# 19_KEY_LED.net
KiCad netlist of a schematic drawn in Altium Designer
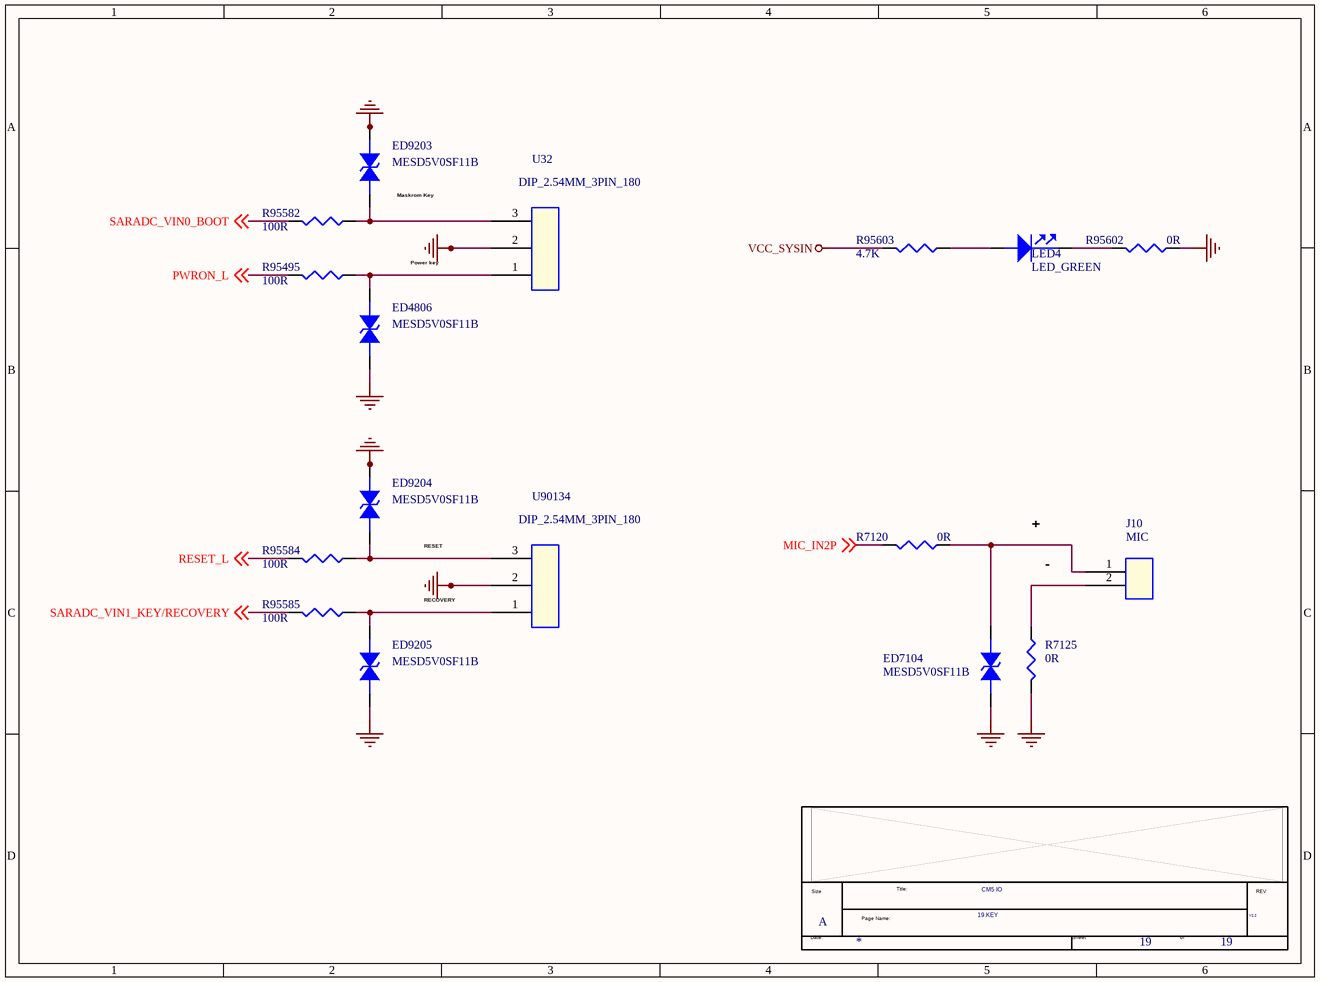
[diagram p0: 19_KEY_LED.SchDoc]

(export (version "E")
  (design (tool "Eeschema 10.0.6"))
  (components
    (comp (ref "*")
      (value "radxa_1010")
      (fields
        (field (name "DOC") "19.KEY")
        (field (name "REVCODE") "V2.2")
        (field (name "TITLE") "CM5 IO")
        (field (name "PAGE SIZE") "A")
        (field (name "PAGE NUMBER") "19")
        (field (name "PAGE COUNT") "19")
      )
      (libsource (lib "*") (part "radxa_1010"))
    )
    (comp (ref "ED4806")
      (value "MESD5V0SF11B")
      (footprint "E0402N")
      (description "ESD Component,5V,30P,SMD,0402")
      (libsource (lib "*") (part "TVS"))
    )
    (comp (ref "ED7104")
      (value "MESD5V0SF11B")
      (footprint "ESD0402")
      (description "1-Line, Bi-directional, Transient Voltage Suppressors.17.5pF.")
      (fields (field (name "MANUFACTURER") "WillSemi(韦尔半导体)") (field (name "CREATED BY") "JJJ"))
      (libsource (lib "*") (part "DIODE BI_DIR TRIG_2"))
    )
    (comp (ref "ED9203")
      (value "MESD5V0SF11B")
      (footprint "E0402N")
      (description "ESD Component,5V,30P,SMD,0402")
      (libsource (lib "*") (part "TVS"))
    )
    (comp (ref "ED9204")
      (value "MESD5V0SF11B")
      (footprint "E0402N")
      (description "ESD Component,5V,30P,SMD,0402")
      (libsource (lib "*") (part "TVS"))
    )
    (comp (ref "ED9205")
      (value "MESD5V0SF11B")
      (footprint "E0402N")
      (description "ESD Component,5V,30P,SMD,0402")
      (libsource (lib "*") (part "TVS"))
    )
    (comp (ref "J10") (value "MIC") (footprint "DIP2PIN-2P54MM") (libsource (lib "*") (part "CON2")))
    (comp (ref "LED4")
      (value "LED_GREEN")
      (footprint "LED0603")
      (description "贴片LED灯，0603，绿色")
      (fields (field (name "CREATED BY") "JJJ"))
      (libsource (lib "*") (part "LED"))
    )
    (comp (ref "R7120")
      (value "0R")
      (footprint "R0402")
      (description "通用厚膜电阻,0R,+/-5%,R0402,1/16W.")
      (fields
        (field (name "TOLERANCE") "5%")
        (field (name "MANUFACTURER") "YAGEO")
        (field (name "CREATED BY") "YTL")
      )
      (libsource (lib "*") (part "RESISTOR_1"))
    )
    (comp (ref "R7125")
      (value "0R")
      (footprint "R0402")
      (description "通用厚膜电阻,2K2,+/-1%,R0402,1/16W.")
      (fields
        (field (name "TOLERANCE") "1%")
        (field (name "MANUFACTURER") "YAGEO")
        (field (name "CREATED BY") "YTL")
      )
      (libsource (lib "*") (part "RESISTOR_1"))
    )
    (comp (ref "R95495")
      (value "100R")
      (footprint "R0402")
      (description "通用厚膜电阻,49K9,+/-1%,R0402,1/16W.")
      (fields
        (field (name "TOLERANCE") "1%")
        (field (name "MANUFACTURER") "YAGEO")
        (field (name "CREATED BY") "YTL")
      )
      (libsource (lib "*") (part "RESISTOR_1_Dup1"))
    )
    (comp (ref "R95582")
      (value "100R")
      (footprint "R0402")
      (description "通用厚膜电阻,49K9,+/-1%,R0402,1/16W.")
      (fields
        (field (name "TOLERANCE") "1%")
        (field (name "MANUFACTURER") "YAGEO")
        (field (name "CREATED BY") "YTL")
      )
      (libsource (lib "*") (part "RESISTOR_1_Dup1"))
    )
    (comp (ref "R95584")
      (value "100R")
      (footprint "R0402")
      (description "通用厚膜电阻,49K9,+/-1%,R0402,1/16W.")
      (fields
        (field (name "TOLERANCE") "1%")
        (field (name "MANUFACTURER") "YAGEO")
        (field (name "CREATED BY") "YTL")
      )
      (libsource (lib "*") (part "RESISTOR_1_Dup1"))
    )
    (comp (ref "R95585")
      (value "100R")
      (footprint "R0402")
      (description "通用厚膜电阻,49K9,+/-1%,R0402,1/16W.")
      (fields
        (field (name "TOLERANCE") "1%")
        (field (name "MANUFACTURER") "YAGEO")
        (field (name "CREATED BY") "YTL")
      )
      (libsource (lib "*") (part "RESISTOR_1_Dup1"))
    )
    (comp (ref "R95602")
      (value "0R")
      (footprint "R0402")
      (description "通用厚膜电阻,49K9,+/-1%,R0402,1/16W.")
      (fields
        (field (name "TOLERANCE") "1%")
        (field (name "MANUFACTURER") "YAGEO")
        (field (name "CREATED BY") "YTL")
      )
      (libsource (lib "*") (part "RESISTOR_1_Dup1"))
    )
    (comp (ref "R95603")
      (value "4.7K")
      (footprint "R0402")
      (description "通用厚膜电阻,49K9,+/-1%,R0402,1/16W.")
      (fields
        (field (name "TOLERANCE") "1%")
        (field (name "MANUFACTURER") "YAGEO")
        (field (name "CREATED BY") "YTL")
      )
      (libsource (lib "*") (part "RESISTOR_1_Dup1"))
    )
    (comp (ref "U32")
      (value "DIP_2.54MM_3PIN_180")
      (footprint "DIP3_1X2P54")
      (libsource (lib "*") (part "CON3_1"))
    )
    (comp (ref "U90134")
      (value "DIP_2.54MM_3PIN_180")
      (footprint "DIP3_1X2P54")
      (libsource (lib "*") (part "CON3_1"))
    )
  )
  (nets
    (net (code "1") (name "GND") (class "Default")
      (node (ref "ED4806") (pin "2") (pinfunction "2_2") (pintype "passive"))
      (node (ref "ED7104") (pin "2") (pinfunction "2_2") (pintype "passive"))
      (node (ref "ED9203") (pin "2") (pinfunction "2_2") (pintype "passive"))
      (node (ref "ED9204") (pin "2") (pinfunction "2_2") (pintype "passive"))
      (node (ref "ED9205") (pin "2") (pinfunction "2_2") (pintype "passive"))
      (node (ref "R7125") (pin "2") (pinfunction "2_2") (pintype "passive"))
      (node (ref "R95602") (pin "2") (pinfunction "2_2") (pintype "passive"))
      (node (ref "U32") (pin "2") (pinfunction "2_2") (pintype "passive"))
      (node (ref "U90134") (pin "2") (pinfunction "2_2") (pintype "passive"))
    )
    (net (code "2") (name "MIC_IN2P") (class "Default")
      (node (ref "R7120") (pin "1") (pinfunction "1_1") (pintype "passive"))
    )
    (net (code "3") (name "Net-(ED4806-Pad1)") (class "Default")
      (node (ref "ED4806") (pin "1") (pinfunction "1_1") (pintype "passive"))
      (node (ref "R95495") (pin "2") (pinfunction "2_2") (pintype "passive"))
      (node (ref "U32") (pin "1") (pinfunction "1_1") (pintype "passive"))
    )
    (net (code "4") (name "Net-(ED7104-Pad1)") (class "Default")
      (node (ref "ED7104") (pin "1") (pinfunction "1_1") (pintype "passive"))
      (node (ref "J10") (pin "1") (pinfunction "1_1") (pintype "passive"))
      (node (ref "R7120") (pin "2") (pinfunction "2_2") (pintype "passive"))
    )
    (net (code "5") (name "Net-(ED9203-Pad1)") (class "Default")
      (node (ref "ED9203") (pin "1") (pinfunction "1_1") (pintype "passive"))
      (node (ref "R95582") (pin "2") (pinfunction "2_2") (pintype "passive"))
      (node (ref "U32") (pin "3") (pinfunction "3_3") (pintype "passive"))
    )
    (net (code "6") (name "Net-(ED9204-Pad1)") (class "Default")
      (node (ref "ED9204") (pin "1") (pinfunction "1_1") (pintype "passive"))
      (node (ref "R95584") (pin "2") (pinfunction "2_2") (pintype "passive"))
      (node (ref "U90134") (pin "3") (pinfunction "3_3") (pintype "passive"))
    )
    (net (code "7") (name "Net-(ED9205-Pad1)") (class "Default")
      (node (ref "ED9205") (pin "1") (pinfunction "1_1") (pintype "passive"))
      (node (ref "R95585") (pin "2") (pinfunction "2_2") (pintype "passive"))
      (node (ref "U90134") (pin "1") (pinfunction "1_1") (pintype "passive"))
    )
    (net (code "8") (name "Net-(J10-Pad2)") (class "Default")
      (node (ref "J10") (pin "2") (pinfunction "2_2") (pintype "passive"))
      (node (ref "R7125") (pin "1") (pinfunction "1_1") (pintype "passive"))
    )
    (net (code "9") (name "Net-(LED4-ANODE)") (class "Default")
      (node (ref "LED4") (pin "1") (pinfunction "ANODE_1") (pintype "passive"))
      (node (ref "R95603") (pin "2") (pinfunction "2_2") (pintype "passive"))
    )
    (net (code "10") (name "Net-(LED4-CATHODE)") (class "Default")
      (node (ref "LED4") (pin "2") (pinfunction "CATHODE_2") (pintype "passive"))
      (node (ref "R95602") (pin "1") (pinfunction "1_1") (pintype "passive"))
    )
    (net (code "11") (name "PWRON_L") (class "Default")
      (node (ref "R95495") (pin "1") (pinfunction "1_1") (pintype "passive"))
    )
    (net (code "12") (name "RESET_L") (class "Default")
      (node (ref "R95584") (pin "1") (pinfunction "1_1") (pintype "passive"))
    )
    (net (code "13") (name "SARADC_VIN0_BOOT") (class "Default")
      (node (ref "R95582") (pin "1") (pinfunction "1_1") (pintype "passive"))
    )
    (net (code "14") (name "SARADC_VIN1_KEY{slash}RECOVERY") (class "Default")
      (node (ref "R95585") (pin "1") (pinfunction "1_1") (pintype "passive"))
    )
    (net (code "15") (name "VCC_SYSIN") (class "Default")
      (node (ref "R95603") (pin "1") (pinfunction "1_1") (pintype "passive"))
    )
  )
)
